# Schematic.net
KiCad netlist of a schematic drawn in Altium Designer
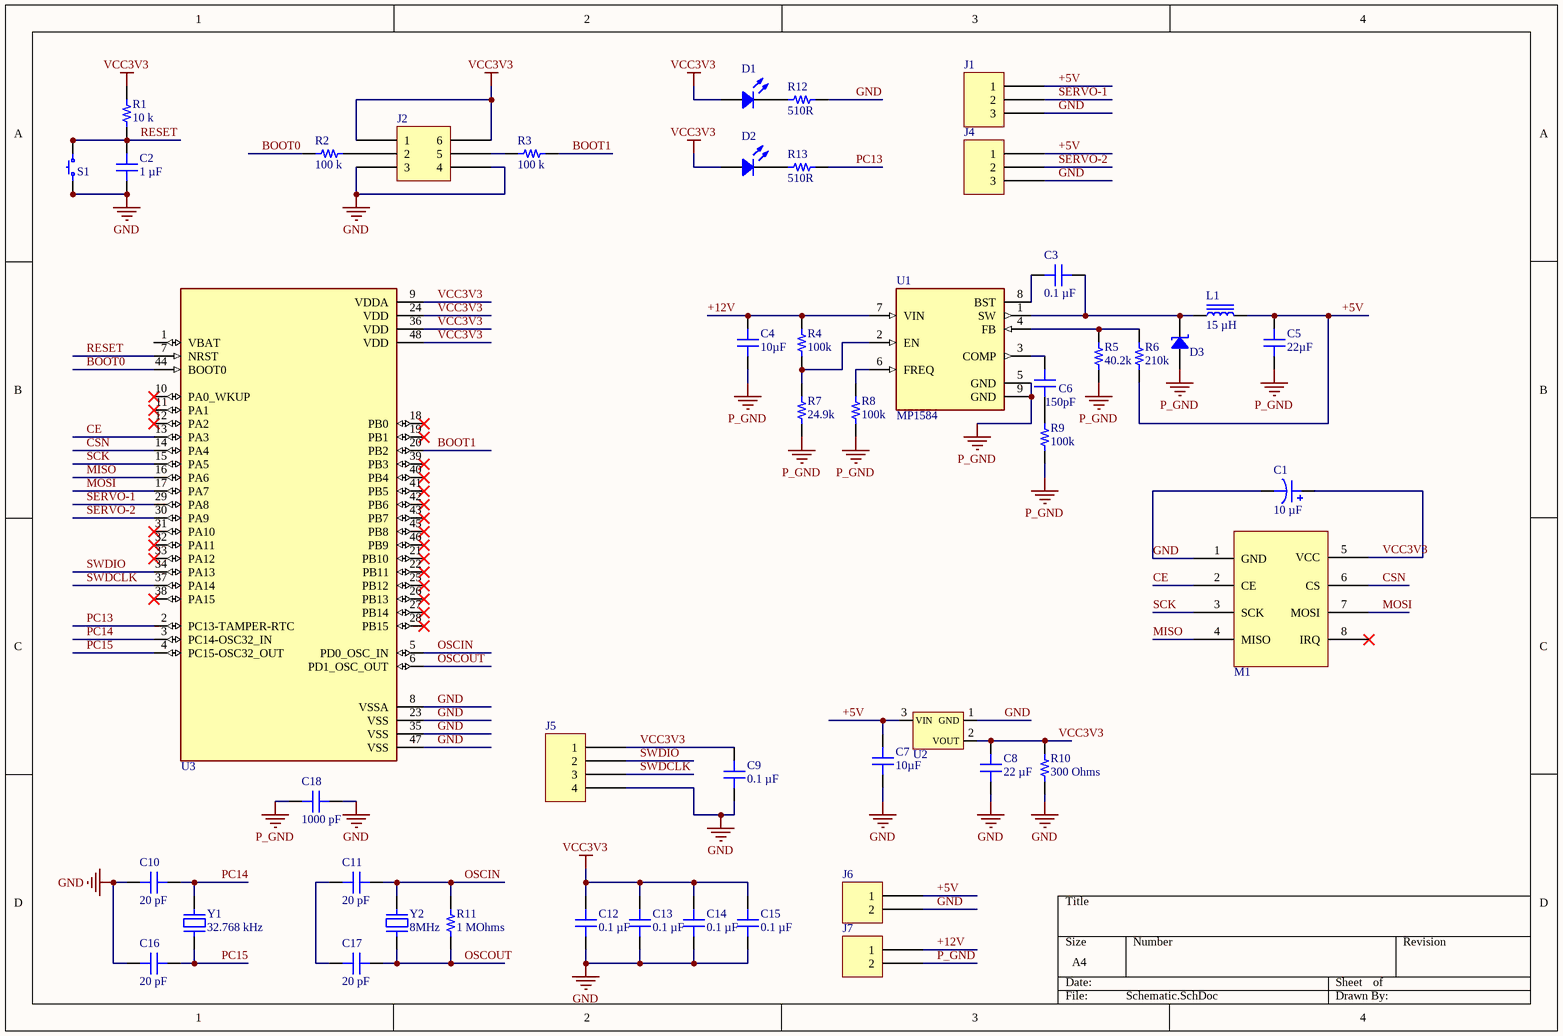
[diagram p0: Schematic.SchDoc]

(export (version "E")
  (design (tool "Eeschema 10.0.6"))
  (components
    (comp (ref "C1")
      (value "10 µF")
      (footprint "CAP ALSMD 4.3MM H5.4MM")
      (description "CAP ALUM 10UF 20% 16V SMD")
      (fields (field (name "PART NUMBER") "UWX1C100MCL1GB") (field (name "MANUFACTURER") "Nichicon"))
      (libsource (lib "Celestial Altium Library - altium_library (1)") (part "Polarised Capacitor"))
    )
    (comp (ref "C2")
      (value "1 µF")
      (footprint "CAP 0603_1608")
      (description "CAP CER 1UF 16V X7R 0603")
      (fields (field (name "PART NUMBER") "C0603C105K4RACAUTO") (field (name "MANUFACTURER") "KEMET"))
      (libsource (lib "Celestial Altium Library - altium_library (1)") (part "Capacitor"))
    )
    (comp (ref "C3")
      (value "0.1 µF")
      (footprint "CAP 0603_1608")
      (description "CAP CER 0.1UF 50V X7R 0603")
      (fields (field (name "PART NUMBER") "C0603C104K5RAC7411") (field (name "MANUFACTURER") "KEMET"))
      (libsource (lib "Celestial Altium Library - altium_library (1)") (part "Capacitor"))
    )
    (comp (ref "C4")
      (value "10µF")
      (footprint "CAP 0805_2012")
      (description "CAP CER 10UF 50V X5R 0805")
      (fields
        (field (name "PART NUMBER") "GRM21BR61H106KE43L")
        (field (name "MANUFACTURER") "Murata Electronics")
      )
      (libsource (lib "Celestial Altium Library - altium_library (1)") (part "Capacitor"))
    )
    (comp (ref "C5")
      (value "22µF")
      (footprint "CAP 0603_1608")
      (description "CAP CER 22UF 6.3V X5R 0603")
      (fields (field (name "PART NUMBER") "06036D226MAT2A") (field (name "MANUFACTURER") "AVX Corporation"))
      (libsource (lib "Celestial Altium Library - altium_library (1)") (part "Capacitor"))
    )
    (comp (ref "C6")
      (value "150pF")
      (footprint "CAP 0603_1608")
      (description "CAP CER 150PF 16V X7R 0603")
      (fields (field (name "PART NUMBER") "885012206029") (field (name "MANUFACTURER") "Würth Elektronik"))
      (libsource (lib "Celestial Altium Library - altium_library (1)") (part "Capacitor"))
    )
    (comp (ref "C7")
      (value "10µF")
      (footprint "CAP 0603_1608")
      (description "CAP CER 10UF 6.3V X5R 0603")
      (fields
        (field (name "PART NUMBER") "GRM188R60J106ME47D")
        (field (name "MANUFACTURER") "Murata Electronics")
      )
      (libsource (lib "Celestial Altium Library - altium_library (1)") (part "Capacitor"))
    )
    (comp (ref "C8")
      (value "22 µF")
      (footprint "CAP 0603_1608")
      (description "CAP CER 22UF 6.3V X5R 0603")
      (fields
        (field (name "PART NUMBER") "GRM186R60J226ME15D")
        (field (name "MANUFACTURER") "Murata Electronics")
      )
      (libsource (lib "Celestial Altium Library - altium_library (1)") (part "Capacitor"))
    )
    (comp (ref "C9")
      (value "0.1 µF")
      (footprint "CAP 0603_1608")
      (description "CAP CER 0.1UF 16V X7R 0603")
      (fields (field (name "PART NUMBER") "CS0603KRX7R7BB104") (field (name "MANUFACTURER") "Yageo"))
      (libsource (lib "Celestial Altium Library - altium_library (1)") (part "Capacitor"))
    )
    (comp (ref "C10")
      (value "20 pF")
      (footprint "CAP 0603_1608")
      (description "CAP CER 20PF 16V NP0 0603")
      (fields (field (name "PART NUMBER") "C0603C200K4GAC7867") (field (name "MANUFACTURER") "KEMET"))
      (libsource (lib "Celestial Altium Library - altium_library (1)") (part "Capacitor"))
    )
    (comp (ref "C11")
      (value "20 pF")
      (footprint "CAP 0603_1608")
      (description "CAP CER 20PF 16V NP0 0603")
      (fields (field (name "PART NUMBER") "C0603C200K4GAC7867") (field (name "MANUFACTURER") "KEMET"))
      (libsource (lib "Celestial Altium Library - altium_library (1)") (part "Capacitor"))
    )
    (comp (ref "C12")
      (value "0.1 µF")
      (footprint "CAP 0603_1608")
      (description "CAP CER 0.1UF 16V X7R 0603")
      (fields (field (name "PART NUMBER") "CS0603KRX7R7BB104") (field (name "MANUFACTURER") "Yageo"))
      (libsource (lib "Celestial Altium Library - altium_library (1)") (part "Capacitor"))
    )
    (comp (ref "C13")
      (value "0.1 µF")
      (footprint "CAP 0603_1608")
      (description "CAP CER 0.1UF 16V X7R 0603")
      (fields (field (name "PART NUMBER") "CS0603KRX7R7BB104") (field (name "MANUFACTURER") "Yageo"))
      (libsource (lib "Celestial Altium Library - altium_library (1)") (part "Capacitor"))
    )
    (comp (ref "C14")
      (value "0.1 µF")
      (footprint "CAP 0603_1608")
      (description "CAP CER 0.1UF 16V X7R 0603")
      (fields (field (name "PART NUMBER") "CS0603KRX7R7BB104") (field (name "MANUFACTURER") "Yageo"))
      (libsource (lib "Celestial Altium Library - altium_library (1)") (part "Capacitor"))
    )
    (comp (ref "C15")
      (value "0.1 µF")
      (footprint "CAP 0603_1608")
      (description "CAP CER 0.1UF 16V X7R 0603")
      (fields (field (name "PART NUMBER") "CS0603KRX7R7BB104") (field (name "MANUFACTURER") "Yageo"))
      (libsource (lib "Celestial Altium Library - altium_library (1)") (part "Capacitor"))
    )
    (comp (ref "C16")
      (value "20 pF")
      (footprint "CAP 0603_1608")
      (description "CAP CER 20PF 16V NP0 0603")
      (fields (field (name "PART NUMBER") "C0603C200K4GAC7867") (field (name "MANUFACTURER") "KEMET"))
      (libsource (lib "Celestial Altium Library - altium_library (1)") (part "Capacitor"))
    )
    (comp (ref "C17")
      (value "20 pF")
      (footprint "CAP 0603_1608")
      (description "CAP CER 20PF 16V NP0 0603")
      (fields (field (name "PART NUMBER") "C0603C200K4GAC7867") (field (name "MANUFACTURER") "KEMET"))
      (libsource (lib "Celestial Altium Library - altium_library (1)") (part "Capacitor"))
    )
    (comp (ref "C18")
      (value "1000 pF")
      (footprint "CAP 0603_1608")
      (description "CAP CER 0603 1NF 16V X7R 10%")
      (fields (field (name "PART NUMBER") "C0603C102K4RECAUTO") (field (name "MANUFACTURER") "KEMET"))
      (libsource (lib "Celestial Altium Library - altium_library (1)") (part "Capacitor"))
    )
    (comp (ref "D1")
      (value "Red")
      (footprint "LED 1206_3216 RED")
      (description "LED RED CLEAR 2SMD")
      (fields (field (name "PART NUMBER") "APTD3216EC") (field (name "MANUFACTURER") "Kingbright"))
      (libsource (lib "Celestial Altium Library - altium_library (1)") (part "LED"))
    )
    (comp (ref "D2")
      (value "Red")
      (footprint "LED 1206_3216 RED")
      (description "LED RED CLEAR 2SMD")
      (fields (field (name "PART NUMBER") "APTD3216EC") (field (name "MANUFACTURER") "Kingbright"))
      (libsource (lib "Celestial Altium Library - altium_library (1)") (part "LED"))
    )
    (comp (ref "D3")
      (value "SMF36A-E3-08")
      (footprint "SMF DO-219AB")
      (description "TVS DIODE 36V 58.1V SMF")
      (fields (field (name "MANUFACTURER") "Vishay Semiconductor Diodes Division"))
      (libsource (lib "Celestial Altium Library - altium_library (1)") (part "DIODE TVS UNI"))
    )
    (comp (ref "J1")
      (value "B3B-PH-K-S(LF)(SN)")
      (footprint "JST B3B-PH-K")
      (description "CONN HEADER VERT 3POS 2MM")
      (fields (field (name "MANUFACTURER") "JST Sales America Inc."))
      (libsource (lib "Celestial Altium Library - altium_library (1)") (part "3 Pin"))
    )
    (comp (ref "J2")
      (value "M20-7830342")
      (footprint "HARWIN M20-7830345")
      (description "CONN RCPT 6POS 0.1 GOLD PCB")
      (fields (field (name "MANUFACTURER") "Harwin Inc."))
      (libsource (lib "Celestial Altium Library - altium_library (1)") (part "2X3 PIN DU"))
    )
    (comp (ref "J4")
      (value "B3B-PH-K-S(LF)(SN)")
      (footprint "JST B3B-PH-K")
      (description "CONN HEADER VERT 3POS 2MM")
      (fields (field (name "MANUFACTURER") "JST Sales America Inc."))
      (libsource (lib "Celestial Altium Library - altium_library (1)") (part "3 Pin"))
    )
    (comp (ref "J5")
      (value "NPPN041BFCN-RC")
      (footprint "SULLINS NPPN041BFCN")
      (description "CONN HDR 4POS 0.079 GOLD PCB")
      (fields (field (name "MANUFACTURER") "Sullins Connector Solutions"))
      (libsource (lib "Celestial Altium Library - altium_library (1)") (part "4 Pin"))
    )
    (comp (ref "J6")
      (value "OQ0232510000G")
      (footprint "FCI 06-381-2PIN")
      (description "TERM BLOCK HDR 2POS 90DEG 3.81MM")
      (fields (field (name "MANUFACTURER") "Amphenol Anytek"))
      (libsource (lib "Celestial Altium Library - altium_library (1)") (part "2 Pin"))
    )
    (comp (ref "J7")
      (value "OQ0232510000G")
      (footprint "FCI 06-381-2PIN")
      (description "TERM BLOCK HDR 2POS 90DEG 3.81MM")
      (fields (field (name "MANUFACTURER") "Amphenol Anytek"))
      (libsource (lib "Celestial Altium Library - altium_library (1)") (part "2 Pin"))
    )
    (comp (ref "L1")
      (value "15 µH")
      (footprint "BOURNS SRR1280")
      (description "FIXED IND 15UH 5.2A 28.5MOHM SMD")
      (fields (field (name "PART NUMBER") "SRR1280-150M") (field (name "MANUFACTURER") "Bourns Inc."))
      (libsource (lib "Celestial Altium Library - altium_library (1)") (part "Inductor"))
    )
    (comp (ref "M1")
      (value "NRF24L01")
      (footprint "NRF24L01")
      (description "NRF24L01+MODULE")
      (fields
        (field (name "MANUFACTURER") "Seeed Studio")
        (field (name "MANUFACTURER PART NUMBER") "113990011")
        (field (name "DESIGNED BY") "Semih AŞÇI")
      )
      (libsource (lib "Integrated_Library1") (part "NRF24L01"))
    )
    (comp (ref "R1")
      (value "10 k")
      (footprint "RES 0603_1608")
      (description "RES 10K OHM 0.1% 1/16W 0603")
      (fields
        (field (name "PART NUMBER") "RNCS0603BKE10K0")
        (field (name "MANUFACTURER") "Stackpole Electronics Inc")
      )
      (libsource (lib "Celestial Altium Library - altium_library (1)") (part "Resistor"))
    )
    (comp (ref "R2")
      (value "100 k")
      (footprint "RES 0603_1608")
      (description "RES 100K OHM 0.1% 1/16W 0603")
      (fields
        (field (name "PART NUMBER") "RNCS0603BKE100K")
        (field (name "MANUFACTURER") "Stackpole Electronics Inc")
      )
      (libsource (lib "Celestial Altium Library - altium_library (1)") (part "Resistor"))
    )
    (comp (ref "R3")
      (value "100 k")
      (footprint "RES 0603_1608")
      (description "RES 100K OHM 0.1% 1/16W 0603")
      (fields
        (field (name "PART NUMBER") "RNCS0603BKE100K")
        (field (name "MANUFACTURER") "Stackpole Electronics Inc")
      )
      (libsource (lib "Celestial Altium Library - altium_library (1)") (part "Resistor"))
    )
    (comp (ref "R4")
      (value "100k")
      (footprint "RES 0603_1608")
      (description "RES 100K OHM 0.1% 1/16W 0603")
      (fields
        (field (name "PART NUMBER") "RNCS0603BKE100K")
        (field (name "MANUFACTURER") "Stackpole Electronics Inc")
      )
      (libsource (lib "Celestial Altium Library - altium_library (1)") (part "Resistor"))
    )
    (comp (ref "R5")
      (value "40.2k")
      (footprint "RES 0603_1608")
      (description "RQ 0603 40K2 0.1% 10PPM 1K RL")
      (fields
        (field (name "PART NUMBER") "RQ73C1J40K2BTDF")
        (field (name "MANUFACTURER") "TE Connectivity Passive Product")
      )
      (libsource (lib "Celestial Altium Library - altium_library (1)") (part "Resistor"))
    )
    (comp (ref "R6")
      (value "210k")
      (footprint "RES 0603_1608")
      (description "RES SMD 210K OHM 0.1% 1/10W 0603")
      (fields (field (name "PART NUMBER") "RT0603BRD07210KL") (field (name "MANUFACTURER") "Yageo"))
      (libsource (lib "Celestial Altium Library - altium_library (1)") (part "Resistor"))
    )
    (comp (ref "R7")
      (value "24.9k")
      (footprint "RES 0603_1608")
      (description "RQ 0603 24K9 0.1% 10PPM 1K RL")
      (fields
        (field (name "PART NUMBER") "RQ73C1J24K9BTDF")
        (field (name "MANUFACTURER") "TE Connectivity Passive Product")
      )
      (libsource (lib "Celestial Altium Library - altium_library (1)") (part "Resistor"))
    )
    (comp (ref "R8")
      (value "100k")
      (footprint "RES 0603_1608")
      (description "RES 100K OHM 0.1% 1/16W 0603")
      (fields
        (field (name "PART NUMBER") "RNCS0603BKE100K")
        (field (name "MANUFACTURER") "Stackpole Electronics Inc")
      )
      (libsource (lib "Celestial Altium Library - altium_library (1)") (part "Resistor"))
    )
    (comp (ref "R9")
      (value "100k")
      (footprint "RES 0603_1608")
      (description "RES 100K OHM 0.1% 1/16W 0603")
      (fields
        (field (name "PART NUMBER") "RNCS0603BKE100K")
        (field (name "MANUFACTURER") "Stackpole Electronics Inc")
      )
      (libsource (lib "Celestial Altium Library - altium_library (1)") (part "Resistor"))
    )
    (comp (ref "R10")
      (value "300 Ohms")
      (footprint "RES 0603_1608")
      (description "RES 300 OHM 5% 1/10W 0603")
      (fields
        (field (name "PART NUMBER") "RMCF0603JT300R")
        (field (name "MANUFACTURER") "Stackpole Electronics Inc")
      )
      (libsource (lib "Celestial Altium Library - altium_library (1)") (part "Resistor"))
    )
    (comp (ref "R11")
      (value "1 MOhms")
      (footprint "RES 0603_1608")
      (description "RES SMD 1M OHM 0.1% 1/10W 0603")
      (fields (field (name "PART NUMBER") "RT0603BRD071ML") (field (name "MANUFACTURER") "Yageo"))
      (libsource (lib "Celestial Altium Library - altium_library (1)") (part "Resistor"))
    )
    (comp (ref "R12")
      (value "510R")
      (footprint "RES 0603_1608")
      (description "RES 510 OHM 5% 1/10W 0603")
      (fields
        (field (name "PART NUMBER") "RMCF0603JT510R")
        (field (name "MANUFACTURER") "Stackpole Electronics Inc")
      )
      (libsource (lib "Celestial Altium Library - altium_library (1)") (part "Resistor"))
    )
    (comp (ref "R13")
      (value "510R")
      (footprint "RES 0603_1608")
      (description "RES 510 OHM 5% 1/10W 0603")
      (fields
        (field (name "PART NUMBER") "RMCF0603JT510R")
        (field (name "MANUFACTURER") "Stackpole Electronics Inc")
      )
      (libsource (lib "Celestial Altium Library - altium_library (1)") (part "Resistor"))
    )
    (comp (ref "S1")
      (value "1-1977223-1")
      (footprint "TE FSM4JSMA")
      (description "SWITCH TACTILE SPST-NO 0.05A 24V")
      (fields (field (name "MANUFACTURER") "TE Connectivity ALCOSWITCH Switches"))
      (libsource (lib "Celestial Altium Library - altium_library (1)") (part "SPST-NO 4 PIN"))
    )
    (comp (ref "U1")
      (value "MP1584")
      (footprint "8-SOIC")
      (description "IC REG BUCK ADJ 3A")
      (fields
        (field (name "MANUFACTURER") "Monolithic Power Systems")
        (field (name "MANUFACTURER PART NUMBER") "MP1584EN-LF-Z")
        (field (name "DESIGNED BY") "Semih AŞÇI")
      )
      (libsource (lib "Integrated_Library1") (part "MP1584EN"))
    )
    (comp (ref "U2")
      (value "AMS1117-3.3V")
      (footprint "SOT223")
      (description "3.3V Voltage regulator")
      (fields
        (field (name "MANUFACTURER PART NUMBER") "AMS1117-3.3")
        (field (name "MANUFACTURER") "Advanced Monolithic Systems")
        (field (name "DESIGNED BY") "Semih AŞÇI")
      )
      (libsource (lib "Integrated_Library1") (part "AMS1117-3.3V SMD"))
    )
    (comp (ref "U3")
      (value "STM32F103C8T6")
      (footprint "QFP50P900X900X160-48N")
      (description "IC MCU 32BIT 64KB FLASH 48LQFP")
      (fields (field (name "MANUFACTURER") "STMicroelectronics") (field (name "DESIGNED BY") "Semih AŞÇI"))
      (libsource (lib "Integrated_Library1") (part "STM32F103C8T6"))
    )
    (comp (ref "Y1")
      (value "32.768 kHz")
      (footprint "ABRACON ABS25")
      (description "CRYSTAL 32.7680KHZ 12.5PF SMD")
      (fields (field (name "PART NUMBER") "ABS25-32.768KHZ-T") (field (name "MANUFACTURER") "Abracon LLC"))
      (libsource (lib "Celestial Altium Library - altium_library (1)") (part "Abracon Crystal ABS25"))
    )
    (comp (ref "Y2")
      (value "8MHz")
      (footprint "ABRACON ABLS")
      (description "CRYSTAL 8.0000MHZ 18PF SMD")
      (fields (field (name "PART NUMBER") "ABLS-8.000MHZ-B4H-T") (field (name "MANUFACTURER") "Abracon LLC"))
      (libsource (lib "Celestial Altium Library - altium_library (1)") (part "Abracon Crystal ABLS"))
    )
  )
  (nets
    (net (code "1") (name "/+5V") (class "Default")
      (node (ref "C5") (pin "2") (pinfunction "2_2") (pintype "passive"))
      (node (ref "C7") (pin "2") (pinfunction "2_2") (pintype "passive"))
      (node (ref "J1") (pin "1") (pinfunction "1_1") (pintype "passive"))
      (node (ref "J4") (pin "1") (pinfunction "1_1") (pintype "passive"))
      (node (ref "J6") (pin "1") (pinfunction "1_1") (pintype "passive"))
      (node (ref "L1") (pin "2") (pinfunction "2_2") (pintype "passive"))
      (node (ref "R6") (pin "1") (pinfunction "1_1") (pintype "passive"))
      (node (ref "U2") (pin "3") (pinfunction "VIN_3") (pintype "passive"))
    )
    (net (code "2") (name "/+12V") (class "Default")
      (node (ref "C4") (pin "2") (pinfunction "2_2") (pintype "passive"))
      (node (ref "J7") (pin "1") (pinfunction "1_1") (pintype "passive"))
      (node (ref "R4") (pin "2") (pinfunction "2_2") (pintype "passive"))
      (node (ref "U1") (pin "7") (pinfunction "VIN_7") (pintype "input"))
    )
    (net (code "3") (name "/BOOT0") (class "Default")
      (node (ref "R2") (pin "1") (pinfunction "1_1") (pintype "passive"))
      (node (ref "U3") (pin "44") (pinfunction "BOOT0_44") (pintype "input"))
    )
    (net (code "4") (name "/BOOT1") (class "Default")
      (node (ref "R3") (pin "2") (pinfunction "2_2") (pintype "passive"))
      (node (ref "U3") (pin "20") (pinfunction "PB2_20") (pintype "bidirectional"))
    )
    (net (code "5") (name "/CE") (class "Default")
      (node (ref "M1") (pin "2") (pinfunction "CE_2") (pintype "passive"))
      (node (ref "U3") (pin "13") (pinfunction "PA3_13") (pintype "bidirectional"))
    )
    (net (code "6") (name "/CSN") (class "Default")
      (node (ref "M1") (pin "6") (pinfunction "CS_6") (pintype "passive"))
      (node (ref "U3") (pin "14") (pinfunction "PA4_14") (pintype "bidirectional"))
    )
    (net (code "7") (name "/MISO") (class "Default")
      (node (ref "M1") (pin "4") (pinfunction "MISO_4") (pintype "passive"))
      (node (ref "U3") (pin "16") (pinfunction "PA6_16") (pintype "bidirectional"))
    )
    (net (code "8") (name "/MOSI") (class "Default")
      (node (ref "M1") (pin "7") (pinfunction "MOSI_7") (pintype "passive"))
      (node (ref "U3") (pin "17") (pinfunction "PA7_17") (pintype "bidirectional"))
    )
    (net (code "9") (name "/OSCIN") (class "Default")
      (node (ref "C11") (pin "2") (pinfunction "2_2") (pintype "passive"))
      (node (ref "R11") (pin "2") (pinfunction "2_2") (pintype "passive"))
      (node (ref "U3") (pin "5") (pinfunction "PD0_OSC_IN_5") (pintype "bidirectional"))
      (node (ref "Y2") (pin "2") (pinfunction "2_2") (pintype "passive"))
    )
    (net (code "10") (name "/OSCOUT") (class "Default")
      (node (ref "C17") (pin "2") (pinfunction "2_2") (pintype "passive"))
      (node (ref "R11") (pin "1") (pinfunction "1_1") (pintype "passive"))
      (node (ref "U3") (pin "6") (pinfunction "PD1_OSC_OUT_6") (pintype "bidirectional"))
      (node (ref "Y2") (pin "1") (pinfunction "1_1") (pintype "passive"))
    )
    (net (code "11") (name "/PC13") (class "Default")
      (node (ref "R13") (pin "2") (pinfunction "2_2") (pintype "passive"))
      (node (ref "U3") (pin "2") (pinfunction "PC13-TAMPER-RTC_2") (pintype "bidirectional"))
    )
    (net (code "12") (name "/PC14") (class "Default")
      (node (ref "C10") (pin "2") (pinfunction "2_2") (pintype "passive"))
      (node (ref "U3") (pin "3") (pinfunction "PC14-OSC32_IN_3") (pintype "bidirectional"))
      (node (ref "Y1") (pin "1") (pinfunction "1_1") (pintype "passive"))
    )
    (net (code "13") (name "/PC15") (class "Default")
      (node (ref "C16") (pin "2") (pinfunction "2_2") (pintype "passive"))
      (node (ref "U3") (pin "4") (pinfunction "PC15-OSC32_OUT_4") (pintype "bidirectional"))
      (node (ref "Y1") (pin "4") (pinfunction "4_4") (pintype "passive"))
    )
    (net (code "14") (name "/RESET") (class "Default")
      (node (ref "C2") (pin "2") (pinfunction "2_2") (pintype "passive"))
      (node (ref "R1") (pin "1") (pinfunction "1_1") (pintype "passive"))
      (node (ref "S1") (pin "3") (pinfunction "3_3") (pintype "passive"))
      (node (ref "S1") (pin "4") (pinfunction "4_4") (pintype "passive"))
      (node (ref "U3") (pin "7") (pinfunction "NRST_7") (pintype "input"))
    )
    (net (code "15") (name "/SCK") (class "Default")
      (node (ref "M1") (pin "3") (pinfunction "SCK_3") (pintype "passive"))
      (node (ref "U3") (pin "15") (pinfunction "PA5_15") (pintype "bidirectional"))
    )
    (net (code "16") (name "/SERVO-1") (class "Default")
      (node (ref "J1") (pin "2") (pinfunction "2_2") (pintype "passive"))
      (node (ref "U3") (pin "29") (pinfunction "PA8_29") (pintype "bidirectional"))
    )
    (net (code "17") (name "/SERVO-2") (class "Default")
      (node (ref "J4") (pin "2") (pinfunction "2_2") (pintype "passive"))
      (node (ref "U3") (pin "30") (pinfunction "PA9_30") (pintype "bidirectional"))
    )
    (net (code "18") (name "/SWDCLK") (class "Default")
      (node (ref "J5") (pin "3") (pinfunction "3_3") (pintype "passive"))
      (node (ref "U3") (pin "37") (pinfunction "PA14_37") (pintype "bidirectional"))
    )
    (net (code "19") (name "/SWDIO") (class "Default")
      (node (ref "J5") (pin "2") (pinfunction "2_2") (pintype "passive"))
      (node (ref "U3") (pin "34") (pinfunction "PA13_34") (pintype "bidirectional"))
    )
    (net (code "20") (name "GND") (class "Default")
      (node (ref "C1") (pin "2") (pinfunction "2_2") (pintype "passive"))
      (node (ref "C10") (pin "1") (pinfunction "1_1") (pintype "passive"))
      (node (ref "C12") (pin "1") (pinfunction "1_1") (pintype "passive"))
      (node (ref "C13") (pin "1") (pinfunction "1_1") (pintype "passive"))
      (node (ref "C14") (pin "1") (pinfunction "1_1") (pintype "passive"))
      (node (ref "C15") (pin "1") (pinfunction "1_1") (pintype "passive"))
      (node (ref "C16") (pin "1") (pinfunction "1_1") (pintype "passive"))
      (node (ref "C18") (pin "2") (pinfunction "2_2") (pintype "passive"))
      (node (ref "C2") (pin "1") (pinfunction "1_1") (pintype "passive"))
      (node (ref "C7") (pin "1") (pinfunction "1_1") (pintype "passive"))
      (node (ref "C8") (pin "1") (pinfunction "1_1") (pintype "passive"))
      (node (ref "C9") (pin "1") (pinfunction "1_1") (pintype "passive"))
      (node (ref "J1") (pin "3") (pinfunction "3_3") (pintype "passive"))
      (node (ref "J2") (pin "3") (pinfunction "3_3") (pintype "passive"))
      (node (ref "J2") (pin "4") (pinfunction "4_4") (pintype "passive"))
      (node (ref "J4") (pin "3") (pinfunction "3_3") (pintype "passive"))
      (node (ref "J5") (pin "4") (pinfunction "4_4") (pintype "passive"))
      (node (ref "J6") (pin "2") (pinfunction "2_2") (pintype "passive"))
      (node (ref "M1") (pin "1") (pinfunction "GND_1") (pintype "passive"))
      (node (ref "R10") (pin "1") (pinfunction "1_1") (pintype "passive"))
      (node (ref "R12") (pin "2") (pinfunction "2_2") (pintype "passive"))
      (node (ref "S1") (pin "1") (pinfunction "1_1") (pintype "passive"))
      (node (ref "S1") (pin "2") (pinfunction "2_2") (pintype "passive"))
      (node (ref "U2") (pin "1") (pinfunction "GND_1") (pintype "passive"))
      (node (ref "U3") (pin "23") (pinfunction "VSS_23") (pintype "power_in"))
      (node (ref "U3") (pin "35") (pinfunction "VSS_35") (pintype "power_in"))
      (node (ref "U3") (pin "47") (pinfunction "VSS_47") (pintype "power_in"))
      (node (ref "U3") (pin "8") (pinfunction "VSSA_8") (pintype "power_in"))
    )
    (net (code "21") (name "Net-(C6-Pad1)") (class "Default")
      (node (ref "C6") (pin "1") (pinfunction "1_1") (pintype "passive"))
      (node (ref "R9") (pin "2") (pinfunction "2_2") (pintype "passive"))
    )
    (net (code "22") (name "Net-(C11-Pad1)") (class "Default")
      (node (ref "C11") (pin "1") (pinfunction "1_1") (pintype "passive"))
      (node (ref "C17") (pin "1") (pinfunction "1_1") (pintype "passive"))
    )
    (net (code "23") (name "Net-(D1-Pad2)") (class "Default")
      (node (ref "D1") (pin "2") (pinfunction "2_2") (pintype "passive"))
      (node (ref "R12") (pin "1") (pinfunction "1_1") (pintype "passive"))
    )
    (net (code "24") (name "Net-(D2-Pad2)") (class "Default")
      (node (ref "D2") (pin "2") (pinfunction "2_2") (pintype "passive"))
      (node (ref "R13") (pin "1") (pinfunction "1_1") (pintype "passive"))
    )
    (net (code "25") (name "Net-(J2-Pad2)") (class "Default")
      (node (ref "J2") (pin "2") (pinfunction "2_2") (pintype "passive"))
      (node (ref "R2") (pin "2") (pinfunction "2_2") (pintype "passive"))
    )
    (net (code "26") (name "Net-(J2-Pad5)") (class "Default")
      (node (ref "J2") (pin "5") (pinfunction "5_5") (pintype "passive"))
      (node (ref "R3") (pin "1") (pinfunction "1_1") (pintype "passive"))
    )
    (net (code "27") (name "Net-(U1-BST)") (class "Default")
      (node (ref "C3") (pin "1") (pinfunction "1_1") (pintype "passive"))
      (node (ref "U1") (pin "8") (pinfunction "BST_8") (pintype "passive"))
    )
    (net (code "28") (name "Net-(U1-COMP)") (class "Default")
      (node (ref "C6") (pin "2") (pinfunction "2_2") (pintype "passive"))
      (node (ref "U1") (pin "3") (pinfunction "COMP_3") (pintype "output"))
    )
    (net (code "29") (name "Net-(U1-EN)") (class "Default")
      (node (ref "R4") (pin "1") (pinfunction "1_1") (pintype "passive"))
      (node (ref "R7") (pin "2") (pinfunction "2_2") (pintype "passive"))
      (node (ref "U1") (pin "2") (pinfunction "EN_2") (pintype "input"))
    )
    (net (code "30") (name "Net-(U1-FB)") (class "Default")
      (node (ref "R5") (pin "2") (pinfunction "2_2") (pintype "passive"))
      (node (ref "R6") (pin "2") (pinfunction "2_2") (pintype "passive"))
      (node (ref "U1") (pin "4") (pinfunction "FB_4") (pintype "input"))
    )
    (net (code "31") (name "Net-(U1-FREQ)") (class "Default")
      (node (ref "R8") (pin "2") (pinfunction "2_2") (pintype "passive"))
      (node (ref "U1") (pin "6") (pinfunction "FREQ_6") (pintype "input"))
    )
    (net (code "32") (name "Net-(U1-SW)") (class "Default")
      (node (ref "C3") (pin "2") (pinfunction "2_2") (pintype "passive"))
      (node (ref "D3") (pin "2") (pinfunction "2_2") (pintype "passive"))
      (node (ref "L1") (pin "1") (pinfunction "1_1") (pintype "passive"))
      (node (ref "U1") (pin "1") (pinfunction "SW_1") (pintype "output"))
    )
    (net (code "33") (name "P_GND") (class "Default")
      (node (ref "C18") (pin "1") (pinfunction "1_1") (pintype "passive"))
      (node (ref "C4") (pin "1") (pinfunction "1_1") (pintype "passive"))
      (node (ref "C5") (pin "1") (pinfunction "1_1") (pintype "passive"))
      (node (ref "D3") (pin "1") (pinfunction "1_1") (pintype "passive"))
      (node (ref "J7") (pin "2") (pinfunction "2_2") (pintype "passive"))
      (node (ref "R5") (pin "1") (pinfunction "1_1") (pintype "passive"))
      (node (ref "R7") (pin "1") (pinfunction "1_1") (pintype "passive"))
      (node (ref "R8") (pin "1") (pinfunction "1_1") (pintype "passive"))
      (node (ref "R9") (pin "1") (pinfunction "1_1") (pintype "passive"))
      (node (ref "U1") (pin "5") (pinfunction "GND_5") (pintype "power_in"))
      (node (ref "U1") (pin "9") (pinfunction "GND_9") (pintype "power_in"))
    )
    (net (code "34") (name "VCC3V3") (class "Default")
      (node (ref "C1") (pin "1") (pinfunction "1_1") (pintype "passive"))
      (node (ref "C12") (pin "2") (pinfunction "2_2") (pintype "passive"))
      (node (ref "C13") (pin "2") (pinfunction "2_2") (pintype "passive"))
      (node (ref "C14") (pin "2") (pinfunction "2_2") (pintype "passive"))
      (node (ref "C15") (pin "2") (pinfunction "2_2") (pintype "passive"))
      (node (ref "C8") (pin "2") (pinfunction "2_2") (pintype "passive"))
      (node (ref "C9") (pin "2") (pinfunction "2_2") (pintype "passive"))
      (node (ref "D1") (pin "1") (pinfunction "1_1") (pintype "passive"))
      (node (ref "D2") (pin "1") (pinfunction "1_1") (pintype "passive"))
      (node (ref "J2") (pin "1") (pinfunction "1_1") (pintype "passive"))
      (node (ref "J2") (pin "6") (pinfunction "6_6") (pintype "passive"))
      (node (ref "J5") (pin "1") (pinfunction "1_1") (pintype "passive"))
      (node (ref "M1") (pin "5") (pinfunction "VCC_5") (pintype "passive"))
      (node (ref "R1") (pin "2") (pinfunction "2_2") (pintype "passive"))
      (node (ref "R10") (pin "2") (pinfunction "2_2") (pintype "passive"))
      (node (ref "U2") (pin "2") (pinfunction "VOUT_2") (pintype "passive"))
      (node (ref "U3") (pin "24") (pinfunction "VDD_24") (pintype "power_in"))
      (node (ref "U3") (pin "36") (pinfunction "VDD_36") (pintype "power_in"))
      (node (ref "U3") (pin "48") (pinfunction "VDD_48") (pintype "power_in"))
      (node (ref "U3") (pin "9") (pinfunction "VDDA_9") (pintype "power_in"))
    )
    (net (code "35") (name "unconnected-(M1-IRQ-Pad8)") (class "Default")
      (node (ref "M1") (pin "8") (pinfunction "IRQ_8") (pintype "passive+no_connect"))
    )
    (net (code "36") (name "unconnected-(U3-PA0_WKUP-Pad10)") (class "Default")
      (node (ref "U3") (pin "10") (pinfunction "PA0_WKUP_10") (pintype "bidirectional+no_connect"))
    )
    (net (code "37") (name "unconnected-(U3-PA1-Pad11)") (class "Default")
      (node (ref "U3") (pin "11") (pinfunction "PA1_11") (pintype "bidirectional+no_connect"))
    )
    (net (code "38") (name "unconnected-(U3-PA2-Pad12)") (class "Default")
      (node (ref "U3") (pin "12") (pinfunction "PA2_12") (pintype "bidirectional+no_connect"))
    )
    (net (code "39") (name "unconnected-(U3-PA10-Pad31)") (class "Default")
      (node (ref "U3") (pin "31") (pinfunction "PA10_31") (pintype "bidirectional+no_connect"))
    )
    (net (code "40") (name "unconnected-(U3-PA11-Pad32)") (class "Default")
      (node (ref "U3") (pin "32") (pinfunction "PA11_32") (pintype "bidirectional+no_connect"))
    )
    (net (code "41") (name "unconnected-(U3-PA12-Pad33)") (class "Default")
      (node (ref "U3") (pin "33") (pinfunction "PA12_33") (pintype "bidirectional+no_connect"))
    )
    (net (code "42") (name "unconnected-(U3-PA15-Pad38)") (class "Default")
      (node (ref "U3") (pin "38") (pinfunction "PA15_38") (pintype "bidirectional+no_connect"))
    )
    (net (code "43") (name "unconnected-(U3-PB0-Pad18)") (class "Default")
      (node (ref "U3") (pin "18") (pinfunction "PB0_18") (pintype "bidirectional+no_connect"))
    )
    (net (code "44") (name "unconnected-(U3-PB1-Pad19)") (class "Default")
      (node (ref "U3") (pin "19") (pinfunction "PB1_19") (pintype "bidirectional+no_connect"))
    )
    (net (code "45") (name "unconnected-(U3-PB3-Pad39)") (class "Default")
      (node (ref "U3") (pin "39") (pinfunction "PB3_39") (pintype "bidirectional+no_connect"))
    )
    (net (code "46") (name "unconnected-(U3-PB4-Pad40)") (class "Default")
      (node (ref "U3") (pin "40") (pinfunction "PB4_40") (pintype "bidirectional+no_connect"))
    )
    (net (code "47") (name "unconnected-(U3-PB5-Pad41)") (class "Default")
      (node (ref "U3") (pin "41") (pinfunction "PB5_41") (pintype "bidirectional+no_connect"))
    )
    (net (code "48") (name "unconnected-(U3-PB6-Pad42)") (class "Default")
      (node (ref "U3") (pin "42") (pinfunction "PB6_42") (pintype "bidirectional+no_connect"))
    )
    (net (code "49") (name "unconnected-(U3-PB7-Pad43)") (class "Default")
      (node (ref "U3") (pin "43") (pinfunction "PB7_43") (pintype "bidirectional+no_connect"))
    )
    (net (code "50") (name "unconnected-(U3-PB8-Pad45)") (class "Default")
      (node (ref "U3") (pin "45") (pinfunction "PB8_45") (pintype "bidirectional+no_connect"))
    )
    (net (code "51") (name "unconnected-(U3-PB9-Pad46)") (class "Default")
      (node (ref "U3") (pin "46") (pinfunction "PB9_46") (pintype "bidirectional+no_connect"))
    )
    (net (code "52") (name "unconnected-(U3-PB10-Pad21)") (class "Default")
      (node (ref "U3") (pin "21") (pinfunction "PB10_21") (pintype "bidirectional+no_connect"))
    )
    (net (code "53") (name "unconnected-(U3-PB11-Pad22)") (class "Default")
      (node (ref "U3") (pin "22") (pinfunction "PB11_22") (pintype "bidirectional+no_connect"))
    )
    (net (code "54") (name "unconnected-(U3-PB12-Pad25)") (class "Default")
      (node (ref "U3") (pin "25") (pinfunction "PB12_25") (pintype "bidirectional+no_connect"))
    )
    (net (code "55") (name "unconnected-(U3-PB13-Pad26)") (class "Default")
      (node (ref "U3") (pin "26") (pinfunction "PB13_26") (pintype "bidirectional+no_connect"))
    )
    (net (code "56") (name "unconnected-(U3-PB14-Pad27)") (class "Default")
      (node (ref "U3") (pin "27") (pinfunction "PB14_27") (pintype "bidirectional+no_connect"))
    )
    (net (code "57") (name "unconnected-(U3-PB15-Pad28)") (class "Default")
      (node (ref "U3") (pin "28") (pinfunction "PB15_28") (pintype "bidirectional+no_connect"))
    )
    (net (code "58") (name "unconnected-(U3-VBAT-Pad1)") (class "Default")
      (node (ref "U3") (pin "1") (pinfunction "VBAT_1") (pintype "bidirectional"))
    )
  )
)
